# Tiny_5_Circle_SMD_-v3.net
KiCad netlist of a schematic drawn in EAGLE
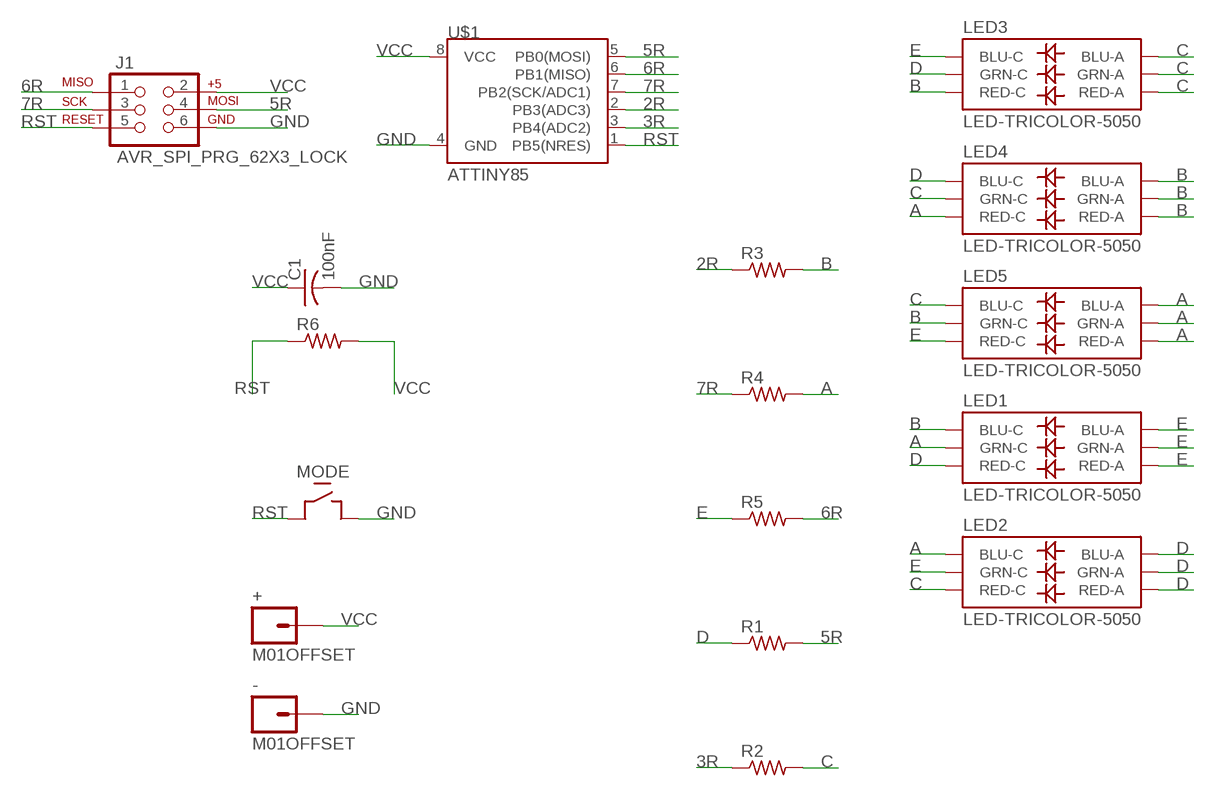
[diagram p0: schematic, sheet 1]

(export (version "E")
  (design (tool "Eeschema 10.0.6"))
  (components
    (comp (ref "+")
      (value "M01OFFSET")
      (footprint "eagle-import:1X01_OFFSET")
      (libsource (lib "eagle-import") (part "M01OFFSET"))
    )
    (comp (ref "-")
      (value "M01OFFSET")
      (footprint "eagle-import:1X01_OFFSET")
      (libsource (lib "eagle-import") (part "M01OFFSET"))
    )
    (comp (ref "C1")
      (value "100nF")
      (footprint "eagle-import:C025-025X050")
      (libsource (lib "eagle-import") (part "C-US025-025X050"))
    )
    (comp (ref "J1")
      (value "AVR_SPI_PRG_62X3_LOCK")
      (footprint "eagle-import:2X3_LOCK")
      (libsource (lib "eagle-import") (part "AVR_SPI_PRG_62X3_LOCK"))
    )
    (comp (ref "LED1")
      (value "LED-TRICOLOR-5050")
      (footprint "eagle-import:LED-TRICOLOR-5050")
      (libsource (lib "eagle-import") (part "LED-TRICOLOR-5050"))
    )
    (comp (ref "LED2")
      (value "LED-TRICOLOR-5050")
      (footprint "eagle-import:LED-TRICOLOR-5050")
      (libsource (lib "eagle-import") (part "LED-TRICOLOR-5050"))
    )
    (comp (ref "LED3")
      (value "LED-TRICOLOR-5050")
      (footprint "eagle-import:LED-TRICOLOR-5050")
      (libsource (lib "eagle-import") (part "LED-TRICOLOR-5050"))
    )
    (comp (ref "LED4")
      (value "LED-TRICOLOR-5050")
      (footprint "eagle-import:LED-TRICOLOR-5050")
      (libsource (lib "eagle-import") (part "LED-TRICOLOR-5050"))
    )
    (comp (ref "LED5")
      (value "LED-TRICOLOR-5050")
      (footprint "eagle-import:LED-TRICOLOR-5050")
      (libsource (lib "eagle-import") (part "LED-TRICOLOR-5050"))
    )
    (comp (ref "MODE")
      (value "3X6MM_SWITCH")
      (footprint "eagle-import:6X3MM-TACT")
      (libsource (lib "eagle-import") (part "3X6MM_SWITCH"))
    )
    (comp (ref "R1")
      (value "R-US_M0805")
      (footprint "eagle-import:M0805")
      (libsource (lib "eagle-import") (part "R-US_M0805"))
    )
    (comp (ref "R2")
      (value "R-US_M0805")
      (footprint "eagle-import:M0805")
      (libsource (lib "eagle-import") (part "R-US_M0805"))
    )
    (comp (ref "R3")
      (value "R-US_M0805")
      (footprint "eagle-import:M0805")
      (libsource (lib "eagle-import") (part "R-US_M0805"))
    )
    (comp (ref "R4")
      (value "R-US_M0805")
      (footprint "eagle-import:M0805")
      (libsource (lib "eagle-import") (part "R-US_M0805"))
    )
    (comp (ref "R5")
      (value "R-US_M0805")
      (footprint "eagle-import:M0805")
      (libsource (lib "eagle-import") (part "R-US_M0805"))
    )
    (comp (ref "R6")
      (value "R-US_M0805")
      (footprint "eagle-import:M0805")
      (libsource (lib "eagle-import") (part "R-US_M0805"))
    )
    (comp (ref "U$1")
      (value "ATTINY85")
      (footprint "eagle-import:SO08-EIAJ")
      (libsource (lib "eagle-import") (part "ATTINY45"))
    )
  )
  (nets
    (net (code "1") (name "/2R") (class "Default")
      (node (ref "R3") (pin "1") (pinfunction "1_1") (pintype "passive"))
      (node (ref "U$1") (pin "2") (pinfunction "PB3(ADC3)_2") (pintype "bidirectional"))
    )
    (net (code "2") (name "/3R") (class "Default")
      (node (ref "R2") (pin "1") (pinfunction "1_1") (pintype "passive"))
      (node (ref "U$1") (pin "3") (pinfunction "PB4(ADC2)_3") (pintype "bidirectional"))
    )
    (net (code "3") (name "/5R") (class "Default")
      (node (ref "J1") (pin "4") (pinfunction "4_4") (pintype "passive"))
      (node (ref "R1") (pin "2") (pinfunction "2_2") (pintype "passive"))
      (node (ref "U$1") (pin "5") (pinfunction "PB0(MOSI)_5") (pintype "bidirectional"))
    )
    (net (code "4") (name "/6R") (class "Default")
      (node (ref "J1") (pin "1") (pinfunction "1_1") (pintype "passive"))
      (node (ref "R5") (pin "2") (pinfunction "2_2") (pintype "passive"))
      (node (ref "U$1") (pin "6") (pinfunction "PB1(MISO)_6") (pintype "bidirectional"))
    )
    (net (code "5") (name "/7R") (class "Default")
      (node (ref "J1") (pin "3") (pinfunction "3_3") (pintype "passive"))
      (node (ref "R4") (pin "1") (pinfunction "1_1") (pintype "passive"))
      (node (ref "U$1") (pin "7") (pinfunction "PB2(SCK/ADC1)_7") (pintype "bidirectional"))
    )
    (net (code "6") (name "/A") (class "Default")
      (node (ref "LED1") (pin "4") (pinfunction "GRN-C_4") (pintype "bidirectional"))
      (node (ref "LED2") (pin "6") (pinfunction "BLU-C_6") (pintype "bidirectional"))
      (node (ref "LED4") (pin "5") (pinfunction "RED-C_5") (pintype "bidirectional"))
      (node (ref "LED5") (pin "1") (pinfunction "BLU-A_1") (pintype "bidirectional"))
      (node (ref "LED5") (pin "2") (pinfunction "RED-A_2") (pintype "bidirectional"))
      (node (ref "LED5") (pin "3") (pinfunction "GRN-A_3") (pintype "bidirectional"))
      (node (ref "R4") (pin "2") (pinfunction "2_2") (pintype "passive"))
    )
    (net (code "7") (name "/B") (class "Default")
      (node (ref "LED1") (pin "6") (pinfunction "BLU-C_6") (pintype "bidirectional"))
      (node (ref "LED3") (pin "5") (pinfunction "RED-C_5") (pintype "bidirectional"))
      (node (ref "LED4") (pin "1") (pinfunction "BLU-A_1") (pintype "bidirectional"))
      (node (ref "LED4") (pin "2") (pinfunction "RED-A_2") (pintype "bidirectional"))
      (node (ref "LED4") (pin "3") (pinfunction "GRN-A_3") (pintype "bidirectional"))
      (node (ref "LED5") (pin "4") (pinfunction "GRN-C_4") (pintype "bidirectional"))
      (node (ref "R3") (pin "2") (pinfunction "2_2") (pintype "passive"))
    )
    (net (code "8") (name "/C") (class "Default")
      (node (ref "LED2") (pin "5") (pinfunction "RED-C_5") (pintype "bidirectional"))
      (node (ref "LED3") (pin "1") (pinfunction "BLU-A_1") (pintype "bidirectional"))
      (node (ref "LED3") (pin "2") (pinfunction "RED-A_2") (pintype "bidirectional"))
      (node (ref "LED3") (pin "3") (pinfunction "GRN-A_3") (pintype "bidirectional"))
      (node (ref "LED4") (pin "4") (pinfunction "GRN-C_4") (pintype "bidirectional"))
      (node (ref "LED5") (pin "6") (pinfunction "BLU-C_6") (pintype "bidirectional"))
      (node (ref "R2") (pin "2") (pinfunction "2_2") (pintype "passive"))
    )
    (net (code "9") (name "/D") (class "Default")
      (node (ref "LED1") (pin "5") (pinfunction "RED-C_5") (pintype "bidirectional"))
      (node (ref "LED2") (pin "1") (pinfunction "BLU-A_1") (pintype "bidirectional"))
      (node (ref "LED2") (pin "2") (pinfunction "RED-A_2") (pintype "bidirectional"))
      (node (ref "LED2") (pin "3") (pinfunction "GRN-A_3") (pintype "bidirectional"))
      (node (ref "LED3") (pin "4") (pinfunction "GRN-C_4") (pintype "bidirectional"))
      (node (ref "LED4") (pin "6") (pinfunction "BLU-C_6") (pintype "bidirectional"))
      (node (ref "R1") (pin "1") (pinfunction "1_1") (pintype "passive"))
    )
    (net (code "10") (name "/E") (class "Default")
      (node (ref "LED1") (pin "1") (pinfunction "BLU-A_1") (pintype "bidirectional"))
      (node (ref "LED1") (pin "2") (pinfunction "RED-A_2") (pintype "bidirectional"))
      (node (ref "LED1") (pin "3") (pinfunction "GRN-A_3") (pintype "bidirectional"))
      (node (ref "LED2") (pin "4") (pinfunction "GRN-C_4") (pintype "bidirectional"))
      (node (ref "LED3") (pin "6") (pinfunction "BLU-C_6") (pintype "bidirectional"))
      (node (ref "LED5") (pin "5") (pinfunction "RED-C_5") (pintype "bidirectional"))
      (node (ref "R5") (pin "1") (pinfunction "1_1") (pintype "passive"))
    )
    (net (code "11") (name "/GND") (class "Default")
      (node (ref "-") (pin "1") (pinfunction "1_1") (pintype "passive"))
      (node (ref "C1") (pin "2") (pinfunction "2_2") (pintype "passive"))
      (node (ref "J1") (pin "6") (pinfunction "6_6") (pintype "passive"))
      (node (ref "MODE") (pin "P$2") (pinfunction "OUT_P$2") (pintype "bidirectional"))
      (node (ref "U$1") (pin "4") (pinfunction "GND_4") (pintype "bidirectional"))
    )
    (net (code "12") (name "/RST") (class "Default")
      (node (ref "J1") (pin "5") (pinfunction "5_5") (pintype "passive"))
      (node (ref "MODE") (pin "P$1") (pinfunction "IN_P$1") (pintype "bidirectional"))
      (node (ref "R6") (pin "1") (pinfunction "1_1") (pintype "passive"))
      (node (ref "U$1") (pin "1") (pinfunction "PB5(NRES)_1") (pintype "bidirectional"))
    )
    (net (code "13") (name "/VCC") (class "Default")
      (node (ref "+") (pin "1") (pinfunction "1_1") (pintype "passive"))
      (node (ref "C1") (pin "1") (pinfunction "1_1") (pintype "passive"))
      (node (ref "J1") (pin "2") (pinfunction "2_2") (pintype "passive"))
      (node (ref "R6") (pin "2") (pinfunction "2_2") (pintype "passive"))
      (node (ref "U$1") (pin "8") (pinfunction "VCC_8") (pintype "bidirectional"))
    )
  )
)
